# Rs232_Interface.net
KiCad netlist of a schematic drawn in Altium Designer
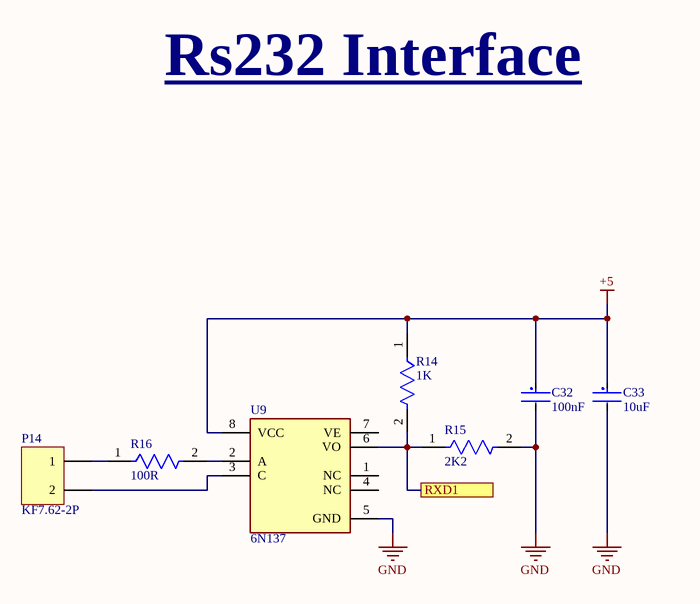
[diagram p0: Rs232_Interface.SchDoc]

(export (version "E")
  (design (tool "Eeschema 10.0.6"))
  (components
    (comp (ref "C32")
      (value "100nF")
      (footprint "Samsung_CL31_IPC_A_1206")
      (description "CAP CER 0.1UF 50V X7R 1206, ±10% 50V Ceramic Capacitor X7R 1206 (3216 Metric)")
      (libsource (lib "DMD_Card") (part "CL31B104KBCNFNC"))
    )
    (comp (ref "C33")
      (value "10uF")
      (footprint "Samsung_CL31_IPC_A_1206")
      (description "CAP CER 10UF 6.3V X5R 1206, ±10% 6.3V Ceramic Capacitor X5R 1206 (3216 Metric)")
      (libsource (lib "DMD_Card") (part "CL31A106KQHNNWE"))
    )
    (comp (ref "P14")
      (value "KF7.62-2P")
      (footprint "KF7.62-2P Barrier Terminal Block")
      (libsource (lib "DMD_Card") (part "KF7.62-2P Barrier Terminal Block"))
    )
    (comp (ref "R14")
      (value "1K")
      (footprint "YAGEO_RC1206-0_65_IPC_A")
      (description "1 ±5% 0.25W, 1/4W Chip Resistor 1206 (3216 Metric) Moisture Resistant Thick Film")
      (libsource (lib "DMD_Card") (part "RC1206JR-071KL"))
    )
    (comp (ref "R15")
      (value "2K2")
      (footprint "YAGEO_RC1206-0_65_IPC_A")
      (fields
        (field (name "MANUFACTURER") "Yageo")
        (field (name "MANUFACTURER PART NUMBER") "RC1206FR-072K2L")
        (field (name "TOLERANCE") "1%")
      )
      (libsource (lib "DMD_Card") (part "RC1206FR-072K2L"))
    )
    (comp (ref "R16")
      (value "100R")
      (footprint "YAGEO_RC1206-0_65_IPC_A")
      (description "100 ±5% 0.25W, 1/4W Chip Resistor 1206 (3216 Metric) Moisture Resistant Thick Film")
      (libsource (lib "DMD_Card") (part "RC1206JR-07100RL"))
    )
    (comp (ref "U9")
      (value "IC_Vishay_6N137_eec")
      (footprint "DIP_08")
      (description "IC OPTOISO 5.3KV 1CH OPN DRAIN 8DIP")
      (fields
        (field (name "MANUFACTURER") "Vishay")
        (field (name "MOUSER PART NUMBER") "782-6N137")
        (field (name "PART NUMBER") "6N137")
      )
      (libsource (lib "DMD_Controller_Card") (part "IC_Vishay_6N137_eec"))
    )
  )
  (nets
    (net (code "1") (name "+5") (class "Default")
      (node (ref "C32") (pin "1") (pinfunction "1_1") (pintype "passive"))
      (node (ref "C33") (pin "1") (pinfunction "1_1") (pintype "passive"))
      (node (ref "R14") (pin "1") (pinfunction "1_1") (pintype "passive"))
      (node (ref "U9") (pin "8") (pinfunction "VCC_8") (pintype "passive"))
    )
    (net (code "2") (name "/RXD1") (class "Default")
      (node (ref "R14") (pin "2") (pinfunction "2_2") (pintype "passive"))
      (node (ref "R15") (pin "1") (pinfunction "1_1") (pintype "passive"))
      (node (ref "U9") (pin "6") (pinfunction "VO_6") (pintype "passive"))
    )
    (net (code "3") (name "GND") (class "Default")
      (node (ref "C32") (pin "2") (pinfunction "2_2") (pintype "passive"))
      (node (ref "C33") (pin "2") (pinfunction "2_2") (pintype "passive"))
      (node (ref "R15") (pin "2") (pinfunction "2_2") (pintype "passive"))
      (node (ref "U9") (pin "5") (pinfunction "GND_5") (pintype "passive"))
    )
    (net (code "4") (name "Net-(P14-Pad1)") (class "Default")
      (node (ref "P14") (pin "1") (pinfunction "1_1") (pintype "passive"))
      (node (ref "R16") (pin "1") (pinfunction "1_1") (pintype "passive"))
    )
    (net (code "5") (name "Net-(U9-A)") (class "Default")
      (node (ref "R16") (pin "2") (pinfunction "2_2") (pintype "passive"))
      (node (ref "U9") (pin "2") (pinfunction "A_2") (pintype "passive"))
    )
    (net (code "6") (name "Net-(U9-C)") (class "Default")
      (node (ref "P14") (pin "2") (pinfunction "2_2") (pintype "passive"))
      (node (ref "U9") (pin "3") (pinfunction "C_3") (pintype "passive"))
    )
    (net (code "7") (name "unconnected-(U9-NC-Pad1)") (class "Default")
      (node (ref "U9") (pin "1") (pinfunction "NC_1") (pintype "passive"))
    )
    (net (code "8") (name "unconnected-(U9-NC-Pad4)") (class "Default")
      (node (ref "U9") (pin "4") (pinfunction "NC_4") (pintype "passive"))
    )
    (net (code "9") (name "unconnected-(U9-VE-Pad7)") (class "Default")
      (node (ref "U9") (pin "7") (pinfunction "VE_7") (pintype "passive"))
    )
  )
)
